# bus_filter.net
KiCad netlist of a schematic drawn in Altium Designer
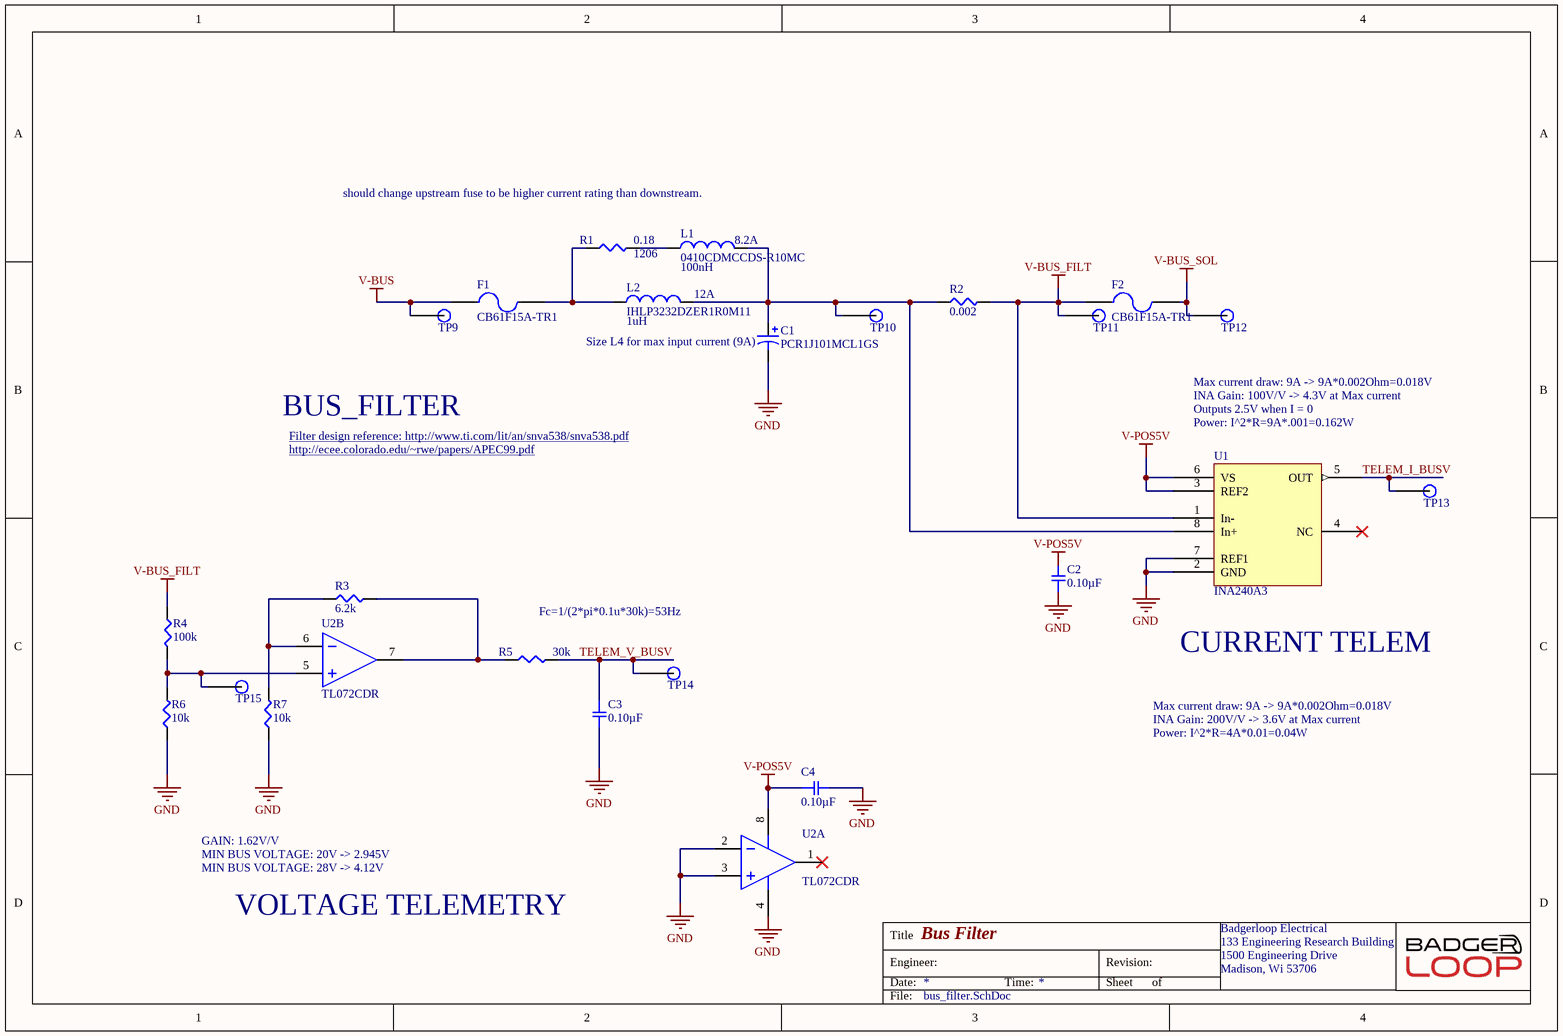
[diagram p0: bus_filter.SchDoc]

(export (version "E")
  (design (tool "Eeschema 10.0.6"))
  (components
    (comp (ref "C1")
      (value "PCR1J101MCL1GS")
      (footprint "CAPAE110103X126M")
      (description "CAP ALUM POLY 100UF 20% 63V SMD")
      (fields (field (name "MANUFACTURER") "Nichicon") (field (name "TOLERANCE") "20%"))
      (libsource (lib "capacitors") (part "PCR1J101MCL1GS"))
    )
    (comp (ref "C2")
      (value "0.10µF")
      (footprint "SMD-0805C")
      (description "CAP CER 0.1UF 10V U2J 0805")
      (fields
        (field (name "DIGI-KEY PART NUMBER") "490-11592-1-ND")
        (field (name "PART NUMBER") "GRM21B7U1A104JA01L")
      )
      (libsource (lib "capacitors") (part "GRM21B7U1A104JA01L"))
    )
    (comp (ref "C3")
      (value "0.10µF")
      (footprint "SMD-0805C")
      (description "CAP CER 0.1UF 16V X7R 0805")
      (fields
        (field (name "DIGI-KEY PART NUMBER") "490-1683-1-ND")
        (field (name "PART NUMBER") "GRM219R71C104KA01D")
      )
      (libsource (lib "capacitors") (part "GRM219R71C104KA01D"))
    )
    (comp (ref "C4")
      (value "0.10µF")
      (footprint "SMD-0805C")
      (description "CAP CER 0.1UF 10V U2J 0805")
      (fields
        (field (name "DIGI-KEY PART NUMBER") "490-11592-1-ND")
        (field (name "PART NUMBER") "GRM21B7U1A104JA01L")
      )
      (libsource (lib "capacitors") (part "GRM21B7U1A104JA01L"))
    )
    (comp (ref "F1")
      (value "CB61F15A-TR1")
      (footprint "RESC6132X26N")
      (fields (field (name "MANUFACTURER") "Eaton"))
      (libsource (lib "misc") (part "CB61F15A-TR1"))
    )
    (comp (ref "F2")
      (value "CB61F15A-TR1")
      (footprint "RESC6132X26N")
      (fields (field (name "MANUFACTURER") "Eaton"))
      (libsource (lib "misc") (part "CB61F15A-TR1"))
    )
    (comp (ref "L1")
      (value "0410CDMCCDS-R10MC")
      (footprint "INDM4442X20N")
      (fields
        (field (name "MANUFACTURER") "Sumida")
        (field (name "INDUCTANCE") "100nH")
        (field (name "SATURATION CURRENT") "8.2A")
      )
      (libsource (lib "inductor") (part "0410CDMCCDS-R10MC"))
    )
    (comp (ref "L2")
      (value "IHLP3232DZER1R0M11")
      (footprint "INDM8682X40N")
      (description "Fixed Inductors 1uH 20% Low Profile")
      (fields
        (field (name "MANUFACTURER") "Vishay Dale")
        (field (name "TOLERANCE") "20%")
        (field (name "SATURATION CURRENT") "12A")
        (field (name "INDUCTANCE") "1uH")
      )
      (libsource (lib "misc") (part "IHLP3232DZER1R0M11"))
    )
    (comp (ref "R1")
      (value "0.18")
      (footprint "SMD-1206-RES")
      (description "RES SMD 0.18 OHM 1% 1/2W 1206")
      (fields
        (field (name "PART NUMBER") "ERJ-8BSFR18V")
        (field (name "DIGI-KEY PART NUMBER") "P17683CT-ND")
        (field (name "SUPPLIER DEVICE PACKAGE") "1206")
      )
      (libsource (lib "resistors") (part "ERJ-8BSFR18V"))
    )
    (comp (ref "R2")
      (value "0.002")
      (footprint "SMD-1206-RES")
      (description "RES SMD 0.002 OHM 1% 1W 1206")
      (fields
        (field (name "MANUFACTURER") "Stackpole Electronics")
        (field (name "MANUFACTURER PART NUMBER") "CSNL1206FT2L00")
      )
      (libsource (lib "resistors") (part "CSNL1206FT2L00TR"))
    )
    (comp (ref "R3")
      (value "6.2k")
      (footprint "SMD-0805-RES")
      (description "RES SMD 6.2K OHM 5% 1/2W 0805")
      (fields
        (field (name "PART NUMBER") "ERJ-P06J622V")
        (field (name "DIGI-KEY PART NUMBER") "P6.2KADCT-ND")
      )
      (libsource (lib "resistors") (part "ERJ-P06J622V"))
    )
    (comp (ref "R4")
      (value "100k")
      (footprint "SMD-0805-RES")
      (description "RES SMD 100K OHM 5% 1/2W 0805")
      (fields
        (field (name "PART NUMBER") "ERJ-P06J104V")
        (field (name "DIGI-KEY PART NUMBER") "P100KADCT-ND")
      )
      (libsource (lib "resistors") (part "ERJ-P06J104V"))
    )
    (comp (ref "R5")
      (value "30k")
      (footprint "SMD-0805-RES")
      (description "RES SMD 30K OHM 1% 1/8W 0805")
      (fields
        (field (name "PART NUMBER") "ERJ-6ENF3002V")
        (field (name "DIGI-KEY PART NUMBER") "P30.0KCCT-ND")
      )
      (libsource (lib "resistors") (part "ERJ-6ENF3002V"))
    )
    (comp (ref "R6")
      (value "10k")
      (footprint "SMD-0805-RES")
      (description "RES SMD 10K OHM 5% 1/2W 0805")
      (fields (field (name "PART NUMBER") "ERJ-P06J103V") (field (name "DIGI-KEY PART NUMBER") "P10KADCT-ND"))
      (libsource (lib "resistors") (part "ERJ-P06J103V"))
    )
    (comp (ref "R7")
      (value "10k")
      (footprint "SMD-0805-RES")
      (description "RES SMD 10K OHM 5% 1/2W 0805")
      (fields (field (name "PART NUMBER") "ERJ-P06J103V") (field (name "DIGI-KEY PART NUMBER") "P10KADCT-ND"))
      (libsource (lib "resistors") (part "ERJ-P06J103V"))
    )
    (comp (ref "TP9")
      (value "TP")
      (footprint "Test Point")
      (description "SMD TEST POINT")
      (libsource (lib "misc") (part "TP"))
    )
    (comp (ref "TP10")
      (value "TP")
      (footprint "Test Point")
      (description "SMD TEST POINT")
      (libsource (lib "misc") (part "TP"))
    )
    (comp (ref "TP11")
      (value "TP")
      (footprint "Test Point")
      (description "SMD TEST POINT")
      (libsource (lib "misc") (part "TP"))
    )
    (comp (ref "TP12")
      (value "TP")
      (footprint "Test Point")
      (description "SMD TEST POINT")
      (libsource (lib "misc") (part "TP"))
    )
    (comp (ref "TP13")
      (value "TP")
      (footprint "Test Point")
      (description "SMD TEST POINT")
      (libsource (lib "misc") (part "TP"))
    )
    (comp (ref "TP14")
      (value "TP")
      (footprint "Test Point")
      (description "SMD TEST POINT")
      (libsource (lib "misc") (part "TP"))
    )
    (comp (ref "TP15")
      (value "TP")
      (footprint "Test Point")
      (description "SMD TEST POINT")
      (libsource (lib "misc") (part "TP"))
    )
    (comp (ref "U1")
      (value "INA240A3")
      (footprint "SOIC127P600X175-8N")
      (description "IC AMP CURRENT SENSE 8-TSSOP 100V/V")
      (fields (field (name "MANUFACTURER") "Texas Instruments"))
      (libsource (lib "ic") (part "INA240A3"))
    )
    (comp (ref "U2")
      (value "TL072CDR")
      (footprint "SOP127P600X175-8N")
      (description "IC OPAMP JFET 3MHZ 8SOIC")
      (fields (field (name "MANUFACTURER") "Texas Instruments"))
      (libsource (lib "ic") (part "TL072CDR"))
    )
  )
  (nets
    (net (code "1") (name "/TELEM_I_BUSV") (class "Default")
      (node (ref "TP13") (pin "1") (pinfunction "1_1") (pintype "passive"))
      (node (ref "U1") (pin "5") (pinfunction "OUT_5") (pintype "output"))
    )
    (net (code "2") (name "/TELEM_V_BUSV") (class "Default")
      (node (ref "C3") (pin "1") (pinfunction "1_1") (pintype "passive"))
      (node (ref "R5") (pin "2") (pinfunction "2_2") (pintype "passive"))
      (node (ref "TP14") (pin "1") (pinfunction "1_1") (pintype "passive"))
    )
    (net (code "3") (name "GND") (class "Default")
      (node (ref "C1") (pin "2") (pinfunction "2_2") (pintype "passive"))
      (node (ref "C2") (pin "1") (pinfunction "1_1") (pintype "passive"))
      (node (ref "C3") (pin "2") (pinfunction "2_2") (pintype "passive"))
      (node (ref "C4") (pin "2") (pinfunction "2_2") (pintype "passive"))
      (node (ref "R6") (pin "1") (pinfunction "1_1") (pintype "passive"))
      (node (ref "R7") (pin "1") (pinfunction "1_1") (pintype "passive"))
      (node (ref "U1") (pin "2") (pinfunction "GND_2") (pintype "power_in"))
      (node (ref "U1") (pin "7") (pinfunction "REF1_7") (pintype "passive"))
      (node (ref "U2") (pin "2") (pinfunction "IN-_2") (pintype "passive"))
      (node (ref "U2") (pin "3") (pinfunction "IN+_3") (pintype "passive"))
      (node (ref "U2") (pin "4") (pinfunction "V-_4") (pintype "power_in"))
    )
    (net (code "4") (name "Net-(F1-Pad2)") (class "Default")
      (node (ref "F1") (pin "2") (pinfunction "2_2") (pintype "passive"))
      (node (ref "L2") (pin "1") (pinfunction "1_1") (pintype "passive"))
      (node (ref "R1") (pin "1") (pinfunction "1_1") (pintype "passive"))
    )
    (net (code "5") (name "Net-(L1-Pad1)") (class "Default")
      (node (ref "L1") (pin "1") (pinfunction "1_1") (pintype "passive"))
      (node (ref "R1") (pin "2") (pinfunction "2_2") (pintype "passive"))
    )
    (net (code "6") (name "Net-(U1-In+)") (class "Default")
      (node (ref "C1") (pin "1") (pinfunction "1_1") (pintype "passive"))
      (node (ref "L1") (pin "2") (pinfunction "2_2") (pintype "passive"))
      (node (ref "L2") (pin "2") (pinfunction "2_2") (pintype "passive"))
      (node (ref "R2") (pin "1") (pinfunction "1_1") (pintype "passive"))
      (node (ref "TP10") (pin "1") (pinfunction "1_1") (pintype "passive"))
      (node (ref "U1") (pin "8") (pinfunction "In+_8") (pintype "passive"))
    )
    (net (code "7") (name "Net-(U2B-IN+)") (class "Default")
      (node (ref "R4") (pin "2") (pinfunction "2_2") (pintype "passive"))
      (node (ref "R6") (pin "2") (pinfunction "2_2") (pintype "passive"))
      (node (ref "TP15") (pin "1") (pinfunction "1_1") (pintype "passive"))
      (node (ref "U2") (pin "5") (pinfunction "IN+_5") (pintype "passive"))
    )
    (net (code "8") (name "Net-(U2B-IN-)") (class "Default")
      (node (ref "R3") (pin "1") (pinfunction "1_1") (pintype "passive"))
      (node (ref "R7") (pin "2") (pinfunction "2_2") (pintype "passive"))
      (node (ref "U2") (pin "6") (pinfunction "IN-_6") (pintype "passive"))
    )
    (net (code "9") (name "Net-(U2B-OUT)") (class "Default")
      (node (ref "R3") (pin "2") (pinfunction "2_2") (pintype "passive"))
      (node (ref "R5") (pin "1") (pinfunction "1_1") (pintype "passive"))
      (node (ref "U2") (pin "7") (pinfunction "OUT_7") (pintype "passive"))
    )
    (net (code "10") (name "V-BUS") (class "Default")
      (node (ref "F1") (pin "1") (pinfunction "1_1") (pintype "passive"))
      (node (ref "TP9") (pin "1") (pinfunction "1_1") (pintype "passive"))
    )
    (net (code "11") (name "V-BUS_FILT") (class "Default")
      (node (ref "F2") (pin "1") (pinfunction "1_1") (pintype "passive"))
      (node (ref "R2") (pin "2") (pinfunction "2_2") (pintype "passive"))
      (node (ref "R4") (pin "1") (pinfunction "1_1") (pintype "passive"))
      (node (ref "TP11") (pin "1") (pinfunction "1_1") (pintype "passive"))
      (node (ref "U1") (pin "1") (pinfunction "In-_1") (pintype "passive"))
    )
    (net (code "12") (name "V-BUS_SOL") (class "Default")
      (node (ref "F2") (pin "2") (pinfunction "2_2") (pintype "passive"))
      (node (ref "TP12") (pin "1") (pinfunction "1_1") (pintype "passive"))
    )
    (net (code "13") (name "V-POS5V") (class "Default")
      (node (ref "C2") (pin "2") (pinfunction "2_2") (pintype "passive"))
      (node (ref "C4") (pin "1") (pinfunction "1_1") (pintype "passive"))
      (node (ref "U1") (pin "3") (pinfunction "REF2_3") (pintype "passive"))
      (node (ref "U1") (pin "6") (pinfunction "VS_6") (pintype "power_in"))
      (node (ref "U2") (pin "8") (pinfunction "V+_8") (pintype "power_in"))
    )
    (net (code "14") (name "unconnected-(U1-NC-Pad4)") (class "Default")
      (node (ref "U1") (pin "4") (pinfunction "NC_4") (pintype "passive+no_connect"))
    )
    (net (code "15") (name "unconnected-(U2A-OUT-Pad1)") (class "Default")
      (node (ref "U2") (pin "1") (pinfunction "OUT_1") (pintype "passive+no_connect"))
    )
  )
)
